# 07-FPGA.net
KiCad netlist of a schematic drawn in Altium Designer
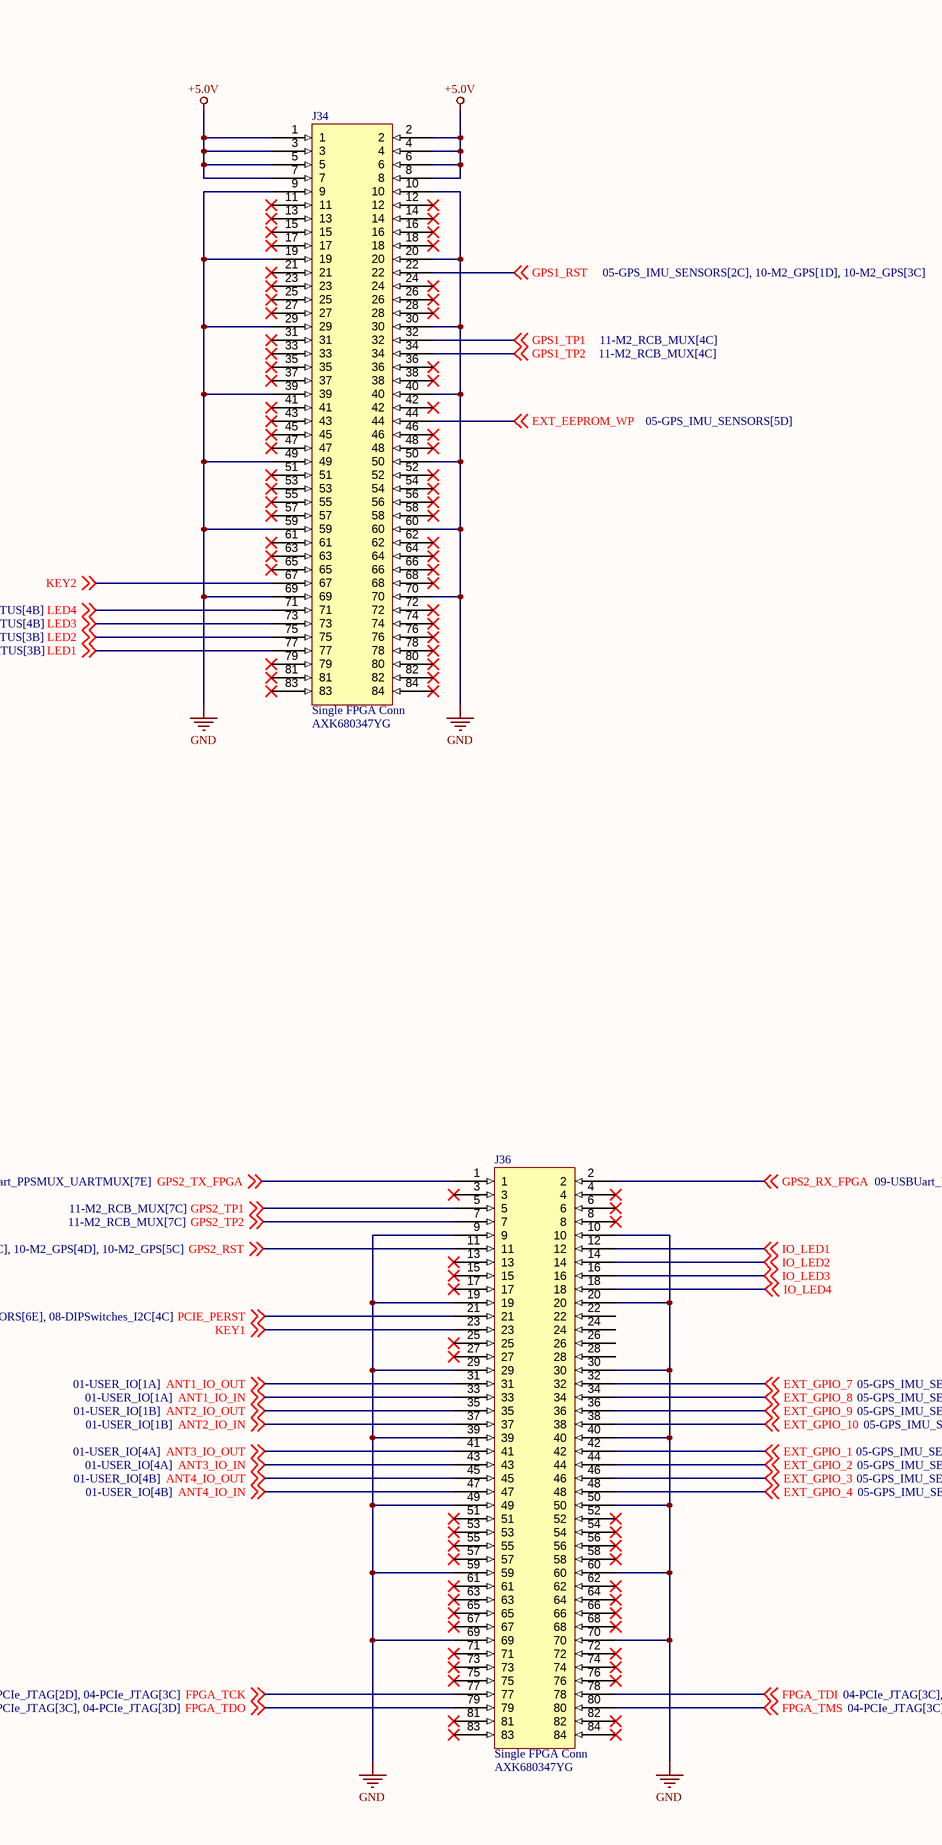
[diagram p0: 07-FPGA.SchDoc, left]
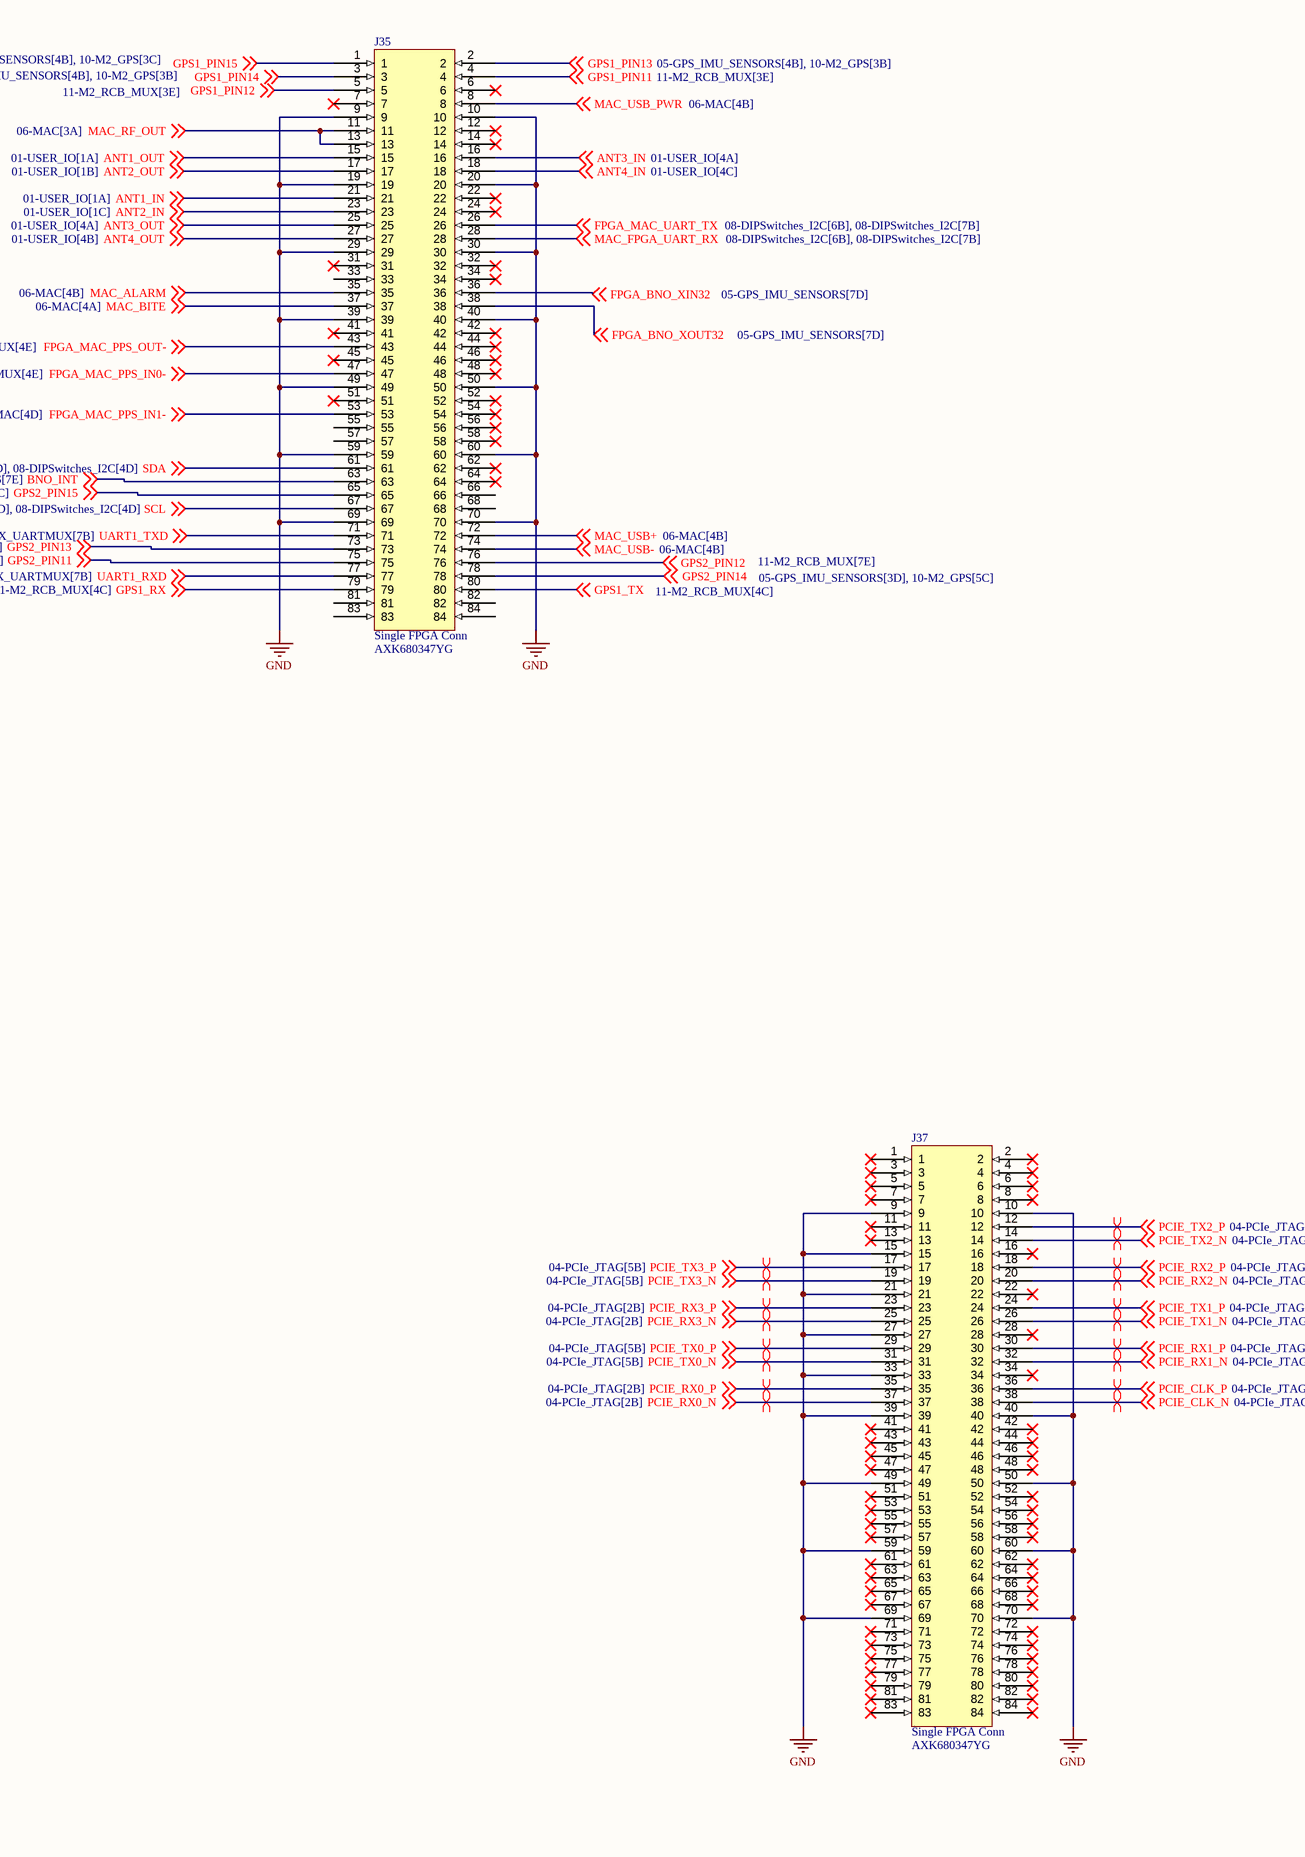
[diagram p1: 07-FPGA.SchDoc, right]

(export (version "E")
  (design (tool "Eeschema 10.0.6"))
  (components
    (comp (ref "J34")
      (value "Single FPGA Conn")
      (footprint "SingleFPGAConn")
      (fields (field (name "PART NUMBER") "AXK680347YG"))
      (libsource (lib "FPGA_CONN") (part "Single FPGA Conn"))
    )
    (comp (ref "J35")
      (value "Single FPGA Conn")
      (footprint "SingleFPGAConn")
      (fields (field (name "PART NUMBER") "AXK680347YG"))
      (libsource (lib "FPGA_CONN") (part "Single FPGA Conn"))
    )
    (comp (ref "J36")
      (value "Single FPGA Conn")
      (footprint "SingleFPGAConn")
      (fields (field (name "PART NUMBER") "AXK680347YG"))
      (libsource (lib "FPGA_CONN") (part "Single FPGA Conn"))
    )
    (comp (ref "J37")
      (value "Single FPGA Conn")
      (footprint "SingleFPGAConn")
      (fields (field (name "PART NUMBER") "AXK680347YG"))
      (libsource (lib "FPGA_CONN") (part "Single FPGA Conn"))
    )
  )
  (nets
    (net (code "1") (name "+5.0V") (class "Default")
      (node (ref "J34") (pin "1") (pinfunction "1_1") (pintype "input"))
      (node (ref "J34") (pin "2") (pinfunction "2_2") (pintype "input"))
      (node (ref "J34") (pin "3") (pinfunction "3_3") (pintype "input"))
      (node (ref "J34") (pin "4") (pinfunction "4_4") (pintype "input"))
      (node (ref "J34") (pin "5") (pinfunction "5_5") (pintype "input"))
      (node (ref "J34") (pin "6") (pinfunction "6_6") (pintype "input"))
      (node (ref "J34") (pin "7") (pinfunction "7_7") (pintype "input"))
      (node (ref "J34") (pin "8") (pinfunction "8_8") (pintype "input"))
    )
    (net (code "2") (name "ANT1_IN") (class "Default")
      (node (ref "J35") (pin "21") (pinfunction "21_21") (pintype "input"))
    )
    (net (code "3") (name "ANT1_IO_IN") (class "Default")
      (node (ref "J36") (pin "33") (pinfunction "33_33") (pintype "input"))
    )
    (net (code "4") (name "ANT1_IO_OUT") (class "Default")
      (node (ref "J36") (pin "31") (pinfunction "31_31") (pintype "input"))
    )
    (net (code "5") (name "ANT1_OUT") (class "Default")
      (node (ref "J35") (pin "15") (pinfunction "15_15") (pintype "input"))
    )
    (net (code "6") (name "ANT2_IN") (class "Default")
      (node (ref "J35") (pin "23") (pinfunction "23_23") (pintype "input"))
    )
    (net (code "7") (name "ANT2_IO_IN") (class "Default")
      (node (ref "J36") (pin "37") (pinfunction "37_37") (pintype "input"))
    )
    (net (code "8") (name "ANT2_IO_OUT") (class "Default")
      (node (ref "J36") (pin "35") (pinfunction "35_35") (pintype "input"))
    )
    (net (code "9") (name "ANT2_OUT") (class "Default")
      (node (ref "J35") (pin "17") (pinfunction "17_17") (pintype "input"))
    )
    (net (code "10") (name "ANT3_IN") (class "Default")
      (node (ref "J35") (pin "16") (pinfunction "16_16") (pintype "input"))
    )
    (net (code "11") (name "ANT3_IO_IN") (class "Default")
      (node (ref "J36") (pin "43") (pinfunction "43_43") (pintype "input"))
    )
    (net (code "12") (name "ANT3_IO_OUT") (class "Default")
      (node (ref "J36") (pin "41") (pinfunction "41_41") (pintype "input"))
    )
    (net (code "13") (name "ANT3_OUT") (class "Default")
      (node (ref "J35") (pin "25") (pinfunction "25_25") (pintype "input"))
    )
    (net (code "14") (name "ANT4_IN") (class "Default")
      (node (ref "J35") (pin "18") (pinfunction "18_18") (pintype "input"))
    )
    (net (code "15") (name "ANT4_IO_IN") (class "Default")
      (node (ref "J36") (pin "47") (pinfunction "47_47") (pintype "input"))
    )
    (net (code "16") (name "ANT4_IO_OUT") (class "Default")
      (node (ref "J36") (pin "45") (pinfunction "45_45") (pintype "input"))
    )
    (net (code "17") (name "ANT4_OUT") (class "Default")
      (node (ref "J35") (pin "27") (pinfunction "27_27") (pintype "input"))
    )
    (net (code "18") (name "BNO_INT") (class "Default")
      (node (ref "J35") (pin "63") (pinfunction "63_63") (pintype "input"))
    )
    (net (code "19") (name "EXT_EEPROM_WP") (class "Default")
      (node (ref "J34") (pin "44") (pinfunction "44_44") (pintype "input"))
    )
    (net (code "20") (name "EXT_GPIO_1") (class "Default")
      (node (ref "J36") (pin "42") (pinfunction "42_42") (pintype "input"))
    )
    (net (code "21") (name "EXT_GPIO_2") (class "Default")
      (node (ref "J36") (pin "44") (pinfunction "44_44") (pintype "input"))
    )
    (net (code "22") (name "EXT_GPIO_3") (class "Default")
      (node (ref "J36") (pin "46") (pinfunction "46_46") (pintype "input"))
    )
    (net (code "23") (name "EXT_GPIO_4") (class "Default")
      (node (ref "J36") (pin "48") (pinfunction "48_48") (pintype "input"))
    )
    (net (code "24") (name "EXT_GPIO_7") (class "Default")
      (node (ref "J36") (pin "32") (pinfunction "32_32") (pintype "input"))
    )
    (net (code "25") (name "EXT_GPIO_8") (class "Default")
      (node (ref "J36") (pin "34") (pinfunction "34_34") (pintype "input"))
    )
    (net (code "26") (name "EXT_GPIO_9") (class "Default")
      (node (ref "J36") (pin "36") (pinfunction "36_36") (pintype "input"))
    )
    (net (code "27") (name "EXT_GPIO_10") (class "Default")
      (node (ref "J36") (pin "38") (pinfunction "38_38") (pintype "input"))
    )
    (net (code "28") (name "FPGA_BNO_XIN32") (class "Default")
      (node (ref "J35") (pin "36") (pinfunction "36_36") (pintype "input"))
    )
    (net (code "29") (name "FPGA_BNO_XOUT32") (class "Default")
      (node (ref "J35") (pin "38") (pinfunction "38_38") (pintype "input"))
    )
    (net (code "30") (name "FPGA_MAC_PPS_IN0-") (class "Default")
      (node (ref "J35") (pin "47") (pinfunction "47_47") (pintype "input"))
    )
    (net (code "31") (name "FPGA_MAC_PPS_IN1-") (class "Default")
      (node (ref "J35") (pin "53") (pinfunction "53_53") (pintype "input"))
    )
    (net (code "32") (name "FPGA_MAC_PPS_OUT-") (class "Default")
      (node (ref "J35") (pin "43") (pinfunction "43_43") (pintype "input"))
    )
    (net (code "33") (name "FPGA_MAC_UART_TX") (class "Default")
      (node (ref "J35") (pin "26") (pinfunction "26_26") (pintype "input"))
    )
    (net (code "34") (name "FPGA_TCK") (class "Default")
      (node (ref "J36") (pin "77") (pinfunction "77_77") (pintype "input"))
    )
    (net (code "35") (name "FPGA_TDI") (class "Default")
      (node (ref "J36") (pin "78") (pinfunction "78_78") (pintype "input"))
    )
    (net (code "36") (name "FPGA_TDO") (class "Default")
      (node (ref "J36") (pin "79") (pinfunction "79_79") (pintype "input"))
    )
    (net (code "37") (name "FPGA_TMS") (class "Default")
      (node (ref "J36") (pin "80") (pinfunction "80_80") (pintype "input"))
    )
    (net (code "38") (name "GND") (class "Default")
      (node (ref "J34") (pin "10") (pinfunction "10_10") (pintype "input"))
      (node (ref "J34") (pin "19") (pinfunction "19_19") (pintype "input"))
      (node (ref "J34") (pin "20") (pinfunction "20_20") (pintype "input"))
      (node (ref "J34") (pin "29") (pinfunction "29_29") (pintype "input"))
      (node (ref "J34") (pin "30") (pinfunction "30_30") (pintype "input"))
      (node (ref "J34") (pin "39") (pinfunction "39_39") (pintype "input"))
      (node (ref "J34") (pin "40") (pinfunction "40_40") (pintype "input"))
      (node (ref "J34") (pin "49") (pinfunction "49_49") (pintype "input"))
      (node (ref "J34") (pin "50") (pinfunction "50_50") (pintype "input"))
      (node (ref "J34") (pin "59") (pinfunction "59_59") (pintype "input"))
      (node (ref "J34") (pin "60") (pinfunction "60_60") (pintype "input"))
      (node (ref "J34") (pin "69") (pinfunction "69_69") (pintype "input"))
      (node (ref "J34") (pin "70") (pinfunction "70_70") (pintype "input"))
      (node (ref "J34") (pin "9") (pinfunction "9_9") (pintype "input"))
      (node (ref "J35") (pin "10") (pinfunction "10_10") (pintype "input"))
      (node (ref "J35") (pin "19") (pinfunction "19_19") (pintype "input"))
      (node (ref "J35") (pin "20") (pinfunction "20_20") (pintype "input"))
      (node (ref "J35") (pin "29") (pinfunction "29_29") (pintype "input"))
      (node (ref "J35") (pin "30") (pinfunction "30_30") (pintype "input"))
      (node (ref "J35") (pin "39") (pinfunction "39_39") (pintype "input"))
      (node (ref "J35") (pin "40") (pinfunction "40_40") (pintype "input"))
      (node (ref "J35") (pin "49") (pinfunction "49_49") (pintype "input"))
      (node (ref "J35") (pin "50") (pinfunction "50_50") (pintype "input"))
      (node (ref "J35") (pin "59") (pinfunction "59_59") (pintype "input"))
      (node (ref "J35") (pin "60") (pinfunction "60_60") (pintype "input"))
      (node (ref "J35") (pin "69") (pinfunction "69_69") (pintype "input"))
      (node (ref "J35") (pin "70") (pinfunction "70_70") (pintype "input"))
      (node (ref "J35") (pin "9") (pinfunction "9_9") (pintype "input"))
      (node (ref "J36") (pin "10") (pinfunction "10_10") (pintype "input"))
      (node (ref "J36") (pin "19") (pinfunction "19_19") (pintype "input"))
      (node (ref "J36") (pin "20") (pinfunction "20_20") (pintype "input"))
      (node (ref "J36") (pin "29") (pinfunction "29_29") (pintype "input"))
      (node (ref "J36") (pin "30") (pinfunction "30_30") (pintype "input"))
      (node (ref "J36") (pin "39") (pinfunction "39_39") (pintype "input"))
      (node (ref "J36") (pin "40") (pinfunction "40_40") (pintype "input"))
      (node (ref "J36") (pin "49") (pinfunction "49_49") (pintype "input"))
      (node (ref "J36") (pin "50") (pinfunction "50_50") (pintype "input"))
      (node (ref "J36") (pin "59") (pinfunction "59_59") (pintype "input"))
      (node (ref "J36") (pin "60") (pinfunction "60_60") (pintype "input"))
      (node (ref "J36") (pin "69") (pinfunction "69_69") (pintype "input"))
      (node (ref "J36") (pin "70") (pinfunction "70_70") (pintype "input"))
      (node (ref "J36") (pin "9") (pinfunction "9_9") (pintype "input"))
      (node (ref "J37") (pin "10") (pinfunction "10_10") (pintype "input"))
      (node (ref "J37") (pin "15") (pinfunction "15_15") (pintype "input"))
      (node (ref "J37") (pin "21") (pinfunction "21_21") (pintype "input"))
      (node (ref "J37") (pin "27") (pinfunction "27_27") (pintype "input"))
      (node (ref "J37") (pin "33") (pinfunction "33_33") (pintype "input"))
      (node (ref "J37") (pin "39") (pinfunction "39_39") (pintype "input"))
      (node (ref "J37") (pin "40") (pinfunction "40_40") (pintype "input"))
      (node (ref "J37") (pin "49") (pinfunction "49_49") (pintype "input"))
      (node (ref "J37") (pin "50") (pinfunction "50_50") (pintype "input"))
      (node (ref "J37") (pin "59") (pinfunction "59_59") (pintype "input"))
      (node (ref "J37") (pin "60") (pinfunction "60_60") (pintype "input"))
      (node (ref "J37") (pin "69") (pinfunction "69_69") (pintype "input"))
      (node (ref "J37") (pin "70") (pinfunction "70_70") (pintype "input"))
      (node (ref "J37") (pin "9") (pinfunction "9_9") (pintype "input"))
    )
    (net (code "39") (name "GPS1_PIN11") (class "Default")
      (node (ref "J35") (pin "4") (pinfunction "4_4") (pintype "input"))
    )
    (net (code "40") (name "GPS1_PIN12") (class "Default")
      (node (ref "J35") (pin "5") (pinfunction "5_5") (pintype "input"))
    )
    (net (code "41") (name "GPS1_PIN13") (class "Default")
      (node (ref "J35") (pin "2") (pinfunction "2_2") (pintype "input"))
    )
    (net (code "42") (name "GPS1_PIN14") (class "Default")
      (node (ref "J35") (pin "3") (pinfunction "3_3") (pintype "input"))
    )
    (net (code "43") (name "GPS1_PIN15") (class "Default")
      (node (ref "J35") (pin "1") (pinfunction "1_1") (pintype "input"))
    )
    (net (code "44") (name "GPS1_RST") (class "Default")
      (node (ref "J34") (pin "22") (pinfunction "22_22") (pintype "input"))
    )
    (net (code "45") (name "GPS1_RX") (class "Default")
      (node (ref "J35") (pin "79") (pinfunction "79_79") (pintype "input"))
    )
    (net (code "46") (name "GPS1_TP1") (class "Default")
      (node (ref "J34") (pin "32") (pinfunction "32_32") (pintype "input"))
    )
    (net (code "47") (name "GPS1_TP2") (class "Default")
      (node (ref "J34") (pin "34") (pinfunction "34_34") (pintype "input"))
    )
    (net (code "48") (name "GPS1_TX") (class "Default")
      (node (ref "J35") (pin "80") (pinfunction "80_80") (pintype "input"))
    )
    (net (code "49") (name "GPS2_PIN11") (class "Default")
      (node (ref "J35") (pin "75") (pinfunction "75_75") (pintype "input"))
    )
    (net (code "50") (name "GPS2_PIN12") (class "Default")
      (node (ref "J35") (pin "76") (pinfunction "76_76") (pintype "input"))
    )
    (net (code "51") (name "GPS2_PIN13") (class "Default")
      (node (ref "J35") (pin "73") (pinfunction "73_73") (pintype "input"))
    )
    (net (code "52") (name "GPS2_PIN14") (class "Default")
      (node (ref "J35") (pin "78") (pinfunction "78_78") (pintype "input"))
    )
    (net (code "53") (name "GPS2_PIN15") (class "Default")
      (node (ref "J35") (pin "65") (pinfunction "65_65") (pintype "input"))
    )
    (net (code "54") (name "GPS2_RST") (class "Default")
      (node (ref "J36") (pin "11") (pinfunction "11_11") (pintype "input"))
    )
    (net (code "55") (name "GPS2_RX_FPGA") (class "Default")
      (node (ref "J36") (pin "2") (pinfunction "2_2") (pintype "input"))
    )
    (net (code "56") (name "GPS2_TP1") (class "Default")
      (node (ref "J36") (pin "5") (pinfunction "5_5") (pintype "input"))
    )
    (net (code "57") (name "GPS2_TP2") (class "Default")
      (node (ref "J36") (pin "7") (pinfunction "7_7") (pintype "input"))
    )
    (net (code "58") (name "GPS2_TX_FPGA") (class "Default")
      (node (ref "J36") (pin "1") (pinfunction "1_1") (pintype "input"))
    )
    (net (code "59") (name "IO_LED1") (class "Default")
      (node (ref "J36") (pin "12") (pinfunction "12_12") (pintype "input"))
    )
    (net (code "60") (name "IO_LED2") (class "Default")
      (node (ref "J36") (pin "14") (pinfunction "14_14") (pintype "input"))
    )
    (net (code "61") (name "IO_LED3") (class "Default")
      (node (ref "J36") (pin "16") (pinfunction "16_16") (pintype "input"))
    )
    (net (code "62") (name "IO_LED4") (class "Default")
      (node (ref "J36") (pin "18") (pinfunction "18_18") (pintype "input"))
    )
    (net (code "63") (name "KEY1") (class "Default")
      (node (ref "J36") (pin "23") (pinfunction "23_23") (pintype "input"))
    )
    (net (code "64") (name "KEY2") (class "Default")
      (node (ref "J34") (pin "67") (pinfunction "67_67") (pintype "input"))
    )
    (net (code "65") (name "LED1") (class "Default")
      (node (ref "J34") (pin "77") (pinfunction "77_77") (pintype "input"))
    )
    (net (code "66") (name "LED2") (class "Default")
      (node (ref "J34") (pin "75") (pinfunction "75_75") (pintype "input"))
    )
    (net (code "67") (name "LED3") (class "Default")
      (node (ref "J34") (pin "73") (pinfunction "73_73") (pintype "input"))
    )
    (net (code "68") (name "LED4") (class "Default")
      (node (ref "J34") (pin "71") (pinfunction "71_71") (pintype "input"))
    )
    (net (code "69") (name "MAC_ALARM") (class "Default")
      (node (ref "J35") (pin "35") (pinfunction "35_35") (pintype "input"))
    )
    (net (code "70") (name "MAC_BITE") (class "Default")
      (node (ref "J35") (pin "37") (pinfunction "37_37") (pintype "input"))
    )
    (net (code "71") (name "MAC_FPGA_UART_RX") (class "Default")
      (node (ref "J35") (pin "28") (pinfunction "28_28") (pintype "input"))
    )
    (net (code "72") (name "MAC_RF_OUT") (class "Default")
      (node (ref "J35") (pin "11") (pinfunction "11_11") (pintype "input"))
      (node (ref "J35") (pin "13") (pinfunction "13_13") (pintype "input"))
    )
    (net (code "73") (name "MAC_USB+") (class "Default")
      (node (ref "J35") (pin "72") (pinfunction "72_72") (pintype "input"))
    )
    (net (code "74") (name "MAC_USB-") (class "Default")
      (node (ref "J35") (pin "74") (pinfunction "74_74") (pintype "input"))
    )
    (net (code "75") (name "MAC_USB_PWR") (class "Default")
      (node (ref "J35") (pin "8") (pinfunction "8_8") (pintype "input"))
    )
    (net (code "76") (name "PCIE_CLK_N") (class "Default")
      (node (ref "J37") (pin "38") (pinfunction "38_38") (pintype "input"))
    )
    (net (code "77") (name "PCIE_CLK_P") (class "Default")
      (node (ref "J37") (pin "36") (pinfunction "36_36") (pintype "input"))
    )
    (net (code "78") (name "PCIE_PERST") (class "Default")
      (node (ref "J36") (pin "21") (pinfunction "21_21") (pintype "input"))
    )
    (net (code "79") (name "PCIE_RX0_N") (class "Default")
      (node (ref "J37") (pin "37") (pinfunction "37_37") (pintype "input"))
    )
    (net (code "80") (name "PCIE_RX0_P") (class "Default")
      (node (ref "J37") (pin "35") (pinfunction "35_35") (pintype "input"))
    )
    (net (code "81") (name "PCIE_RX1_N") (class "Default")
      (node (ref "J37") (pin "32") (pinfunction "32_32") (pintype "input"))
    )
    (net (code "82") (name "PCIE_RX1_P") (class "Default")
      (node (ref "J37") (pin "30") (pinfunction "30_30") (pintype "input"))
    )
    (net (code "83") (name "PCIE_RX2_N") (class "Default")
      (node (ref "J37") (pin "20") (pinfunction "20_20") (pintype "input"))
    )
    (net (code "84") (name "PCIE_RX2_P") (class "Default")
      (node (ref "J37") (pin "18") (pinfunction "18_18") (pintype "input"))
    )
    (net (code "85") (name "PCIE_RX3_N") (class "Default")
      (node (ref "J37") (pin "25") (pinfunction "25_25") (pintype "input"))
    )
    (net (code "86") (name "PCIE_RX3_P") (class "Default")
      (node (ref "J37") (pin "23") (pinfunction "23_23") (pintype "input"))
    )
    (net (code "87") (name "PCIE_TX0_N") (class "Default")
      (node (ref "J37") (pin "31") (pinfunction "31_31") (pintype "input"))
    )
    (net (code "88") (name "PCIE_TX0_P") (class "Default")
      (node (ref "J37") (pin "29") (pinfunction "29_29") (pintype "input"))
    )
    (net (code "89") (name "PCIE_TX1_N") (class "Default")
      (node (ref "J37") (pin "26") (pinfunction "26_26") (pintype "input"))
    )
    (net (code "90") (name "PCIE_TX1_P") (class "Default")
      (node (ref "J37") (pin "24") (pinfunction "24_24") (pintype "input"))
    )
    (net (code "91") (name "PCIE_TX2_N") (class "Default")
      (node (ref "J37") (pin "14") (pinfunction "14_14") (pintype "input"))
    )
    (net (code "92") (name "PCIE_TX2_P") (class "Default")
      (node (ref "J37") (pin "12") (pinfunction "12_12") (pintype "input"))
    )
    (net (code "93") (name "PCIE_TX3_N") (class "Default")
      (node (ref "J37") (pin "19") (pinfunction "19_19") (pintype "input"))
    )
    (net (code "94") (name "PCIE_TX3_P") (class "Default")
      (node (ref "J37") (pin "17") (pinfunction "17_17") (pintype "input"))
    )
    (net (code "95") (name "SCL") (class "Default")
      (node (ref "J35") (pin "67") (pinfunction "67_67") (pintype "input"))
    )
    (net (code "96") (name "SDA") (class "Default")
      (node (ref "J35") (pin "61") (pinfunction "61_61") (pintype "input"))
    )
    (net (code "97") (name "UART1_RXD") (class "Default")
      (node (ref "J35") (pin "77") (pinfunction "77_77") (pintype "input"))
    )
    (net (code "98") (name "UART1_TXD") (class "Default")
      (node (ref "J35") (pin "71") (pinfunction "71_71") (pintype "input"))
    )
    (net (code "99") (name "unconnected-(J34-Pad11)") (class "Default")
      (node (ref "J34") (pin "11") (pinfunction "11_11") (pintype "input+no_connect"))
    )
    (net (code "100") (name "unconnected-(J34-Pad12)") (class "Default")
      (node (ref "J34") (pin "12") (pinfunction "12_12") (pintype "input+no_connect"))
    )
    (net (code "101") (name "unconnected-(J34-Pad13)") (class "Default")
      (node (ref "J34") (pin "13") (pinfunction "13_13") (pintype "input+no_connect"))
    )
    (net (code "102") (name "unconnected-(J34-Pad14)") (class "Default")
      (node (ref "J34") (pin "14") (pinfunction "14_14") (pintype "input+no_connect"))
    )
    (net (code "103") (name "unconnected-(J34-Pad15)") (class "Default")
      (node (ref "J34") (pin "15") (pinfunction "15_15") (pintype "input+no_connect"))
    )
    (net (code "104") (name "unconnected-(J34-Pad16)") (class "Default")
      (node (ref "J34") (pin "16") (pinfunction "16_16") (pintype "input+no_connect"))
    )
    (net (code "105") (name "unconnected-(J34-Pad17)") (class "Default")
      (node (ref "J34") (pin "17") (pinfunction "17_17") (pintype "input+no_connect"))
    )
    (net (code "106") (name "unconnected-(J34-Pad18)") (class "Default")
      (node (ref "J34") (pin "18") (pinfunction "18_18") (pintype "input+no_connect"))
    )
    (net (code "107") (name "unconnected-(J34-Pad21)") (class "Default")
      (node (ref "J34") (pin "21") (pinfunction "21_21") (pintype "input+no_connect"))
    )
    (net (code "108") (name "unconnected-(J34-Pad23)") (class "Default")
      (node (ref "J34") (pin "23") (pinfunction "23_23") (pintype "input+no_connect"))
    )
    (net (code "109") (name "unconnected-(J34-Pad24)") (class "Default")
      (node (ref "J34") (pin "24") (pinfunction "24_24") (pintype "input+no_connect"))
    )
    (net (code "110") (name "unconnected-(J34-Pad25)") (class "Default")
      (node (ref "J34") (pin "25") (pinfunction "25_25") (pintype "input+no_connect"))
    )
    (net (code "111") (name "unconnected-(J34-Pad26)") (class "Default")
      (node (ref "J34") (pin "26") (pinfunction "26_26") (pintype "input+no_connect"))
    )
    (net (code "112") (name "unconnected-(J34-Pad27)") (class "Default")
      (node (ref "J34") (pin "27") (pinfunction "27_27") (pintype "input+no_connect"))
    )
    (net (code "113") (name "unconnected-(J34-Pad28)") (class "Default")
      (node (ref "J34") (pin "28") (pinfunction "28_28") (pintype "input+no_connect"))
    )
    (net (code "114") (name "unconnected-(J34-Pad31)") (class "Default")
      (node (ref "J34") (pin "31") (pinfunction "31_31") (pintype "input+no_connect"))
    )
    (net (code "115") (name "unconnected-(J34-Pad33)") (class "Default")
      (node (ref "J34") (pin "33") (pinfunction "33_33") (pintype "input+no_connect"))
    )
    (net (code "116") (name "unconnected-(J34-Pad35)") (class "Default")
      (node (ref "J34") (pin "35") (pinfunction "35_35") (pintype "input+no_connect"))
    )
    (net (code "117") (name "unconnected-(J34-Pad36)") (class "Default")
      (node (ref "J34") (pin "36") (pinfunction "36_36") (pintype "input+no_connect"))
    )
    (net (code "118") (name "unconnected-(J34-Pad37)") (class "Default")
      (node (ref "J34") (pin "37") (pinfunction "37_37") (pintype "input+no_connect"))
    )
    (net (code "119") (name "unconnected-(J34-Pad38)") (class "Default")
      (node (ref "J34") (pin "38") (pinfunction "38_38") (pintype "input+no_connect"))
    )
    (net (code "120") (name "unconnected-(J34-Pad41)") (class "Default")
      (node (ref "J34") (pin "41") (pinfunction "41_41") (pintype "input+no_connect"))
    )
    (net (code "121") (name "unconnected-(J34-Pad42)") (class "Default")
      (node (ref "J34") (pin "42") (pinfunction "42_42") (pintype "input+no_connect"))
    )
    (net (code "122") (name "unconnected-(J34-Pad43)") (class "Default")
      (node (ref "J34") (pin "43") (pinfunction "43_43") (pintype "input+no_connect"))
    )
    (net (code "123") (name "unconnected-(J34-Pad45)") (class "Default")
      (node (ref "J34") (pin "45") (pinfunction "45_45") (pintype "input+no_connect"))
    )
    (net (code "124") (name "unconnected-(J34-Pad46)") (class "Default")
      (node (ref "J34") (pin "46") (pinfunction "46_46") (pintype "input+no_connect"))
    )
    (net (code "125") (name "unconnected-(J34-Pad47)") (class "Default")
      (node (ref "J34") (pin "47") (pinfunction "47_47") (pintype "input+no_connect"))
    )
    (net (code "126") (name "unconnected-(J34-Pad48)") (class "Default")
      (node (ref "J34") (pin "48") (pinfunction "48_48") (pintype "input+no_connect"))
    )
    (net (code "127") (name "unconnected-(J34-Pad51)") (class "Default")
      (node (ref "J34") (pin "51") (pinfunction "51_51") (pintype "input+no_connect"))
    )
    (net (code "128") (name "unconnected-(J34-Pad52)") (class "Default")
      (node (ref "J34") (pin "52") (pinfunction "52_52") (pintype "input+no_connect"))
    )
    (net (code "129") (name "unconnected-(J34-Pad53)") (class "Default")
      (node (ref "J34") (pin "53") (pinfunction "53_53") (pintype "input+no_connect"))
    )
    (net (code "130") (name "unconnected-(J34-Pad54)") (class "Default")
      (node (ref "J34") (pin "54") (pinfunction "54_54") (pintype "input+no_connect"))
    )
    (net (code "131") (name "unconnected-(J34-Pad55)") (class "Default")
      (node (ref "J34") (pin "55") (pinfunction "55_55") (pintype "input+no_connect"))
    )
    (net (code "132") (name "unconnected-(J34-Pad56)") (class "Default")
      (node (ref "J34") (pin "56") (pinfunction "56_56") (pintype "input+no_connect"))
    )
    (net (code "133") (name "unconnected-(J34-Pad57)") (class "Default")
      (node (ref "J34") (pin "57") (pinfunction "57_57") (pintype "input+no_connect"))
    )
    (net (code "134") (name "unconnected-(J34-Pad58)") (class "Default")
      (node (ref "J34") (pin "58") (pinfunction "58_58") (pintype "input+no_connect"))
    )
    (net (code "135") (name "unconnected-(J34-Pad61)") (class "Default")
      (node (ref "J34") (pin "61") (pinfunction "61_61") (pintype "input+no_connect"))
    )
    (net (code "136") (name "unconnected-(J34-Pad62)") (class "Default")
      (node (ref "J34") (pin "62") (pinfunction "62_62") (pintype "input+no_connect"))
    )
    (net (code "137") (name "unconnected-(J34-Pad63)") (class "Default")
      (node (ref "J34") (pin "63") (pinfunction "63_63") (pintype "input+no_connect"))
    )
    (net (code "138") (name "unconnected-(J34-Pad64)") (class "Default")
      (node (ref "J34") (pin "64") (pinfunction "64_64") (pintype "input+no_connect"))
    )
    (net (code "139") (name "unconnected-(J34-Pad65)") (class "Default")
      (node (ref "J34") (pin "65") (pinfunction "65_65") (pintype "input+no_connect"))
    )
    (net (code "140") (name "unconnected-(J34-Pad66)") (class "Default")
      (node (ref "J34") (pin "66") (pinfunction "66_66") (pintype "input+no_connect"))
    )
    (net (code "141") (name "unconnected-(J34-Pad68)") (class "Default")
      (node (ref "J34") (pin "68") (pinfunction "68_68") (pintype "input+no_connect"))
    )
    (net (code "142") (name "unconnected-(J34-Pad72)") (class "Default")
      (node (ref "J34") (pin "72") (pinfunction "72_72") (pintype "input+no_connect"))
    )
    (net (code "143") (name "unconnected-(J34-Pad74)") (class "Default")
      (node (ref "J34") (pin "74") (pinfunction "74_74") (pintype "input+no_connect"))
    )
    (net (code "144") (name "unconnected-(J34-Pad76)") (class "Default")
      (node (ref "J34") (pin "76") (pinfunction "76_76") (pintype "input+no_connect"))
    )
    (net (code "145") (name "unconnected-(J34-Pad78)") (class "Default")
      (node (ref "J34") (pin "78") (pinfunction "78_78") (pintype "input+no_connect"))
    )
    (net (code "146") (name "unconnected-(J34-Pad79)") (class "Default")
      (node (ref "J34") (pin "79") (pinfunction "79_79") (pintype "input+no_connect"))
    )
    (net (code "147") (name "unconnected-(J34-Pad80)") (class "Default")
      (node (ref "J34") (pin "80") (pinfunction "80_80") (pintype "input+no_connect"))
    )
    (net (code "148") (name "unconnected-(J34-Pad81)") (class "Default")
      (node (ref "J34") (pin "81") (pinfunction "81_81") (pintype "input+no_connect"))
    )
    (net (code "149") (name "unconnected-(J34-Pad82)") (class "Default")
      (node (ref "J34") (pin "82") (pinfunction "82_82") (pintype "input+no_connect"))
    )
    (net (code "150") (name "unconnected-(J34-Pad83)") (class "Default")
      (node (ref "J34") (pin "83") (pinfunction "83_83") (pintype "input+no_connect"))
    )
    (net (code "151") (name "unconnected-(J34-Pad84)") (class "Default")
      (node (ref "J34") (pin "84") (pinfunction "84_84") (pintype "input+no_connect"))
    )
    (net (code "152") (name "unconnected-(J35-Pad6)") (class "Default")
      (node (ref "J35") (pin "6") (pinfunction "6_6") (pintype "input+no_connect"))
    )
    (net (code "153") (name "unconnected-(J35-Pad7)") (class "Default")
      (node (ref "J35") (pin "7") (pinfunction "7_7") (pintype "input+no_connect"))
    )
    (net (code "154") (name "unconnected-(J35-Pad12)") (class "Default")
      (node (ref "J35") (pin "12") (pinfunction "12_12") (pintype "input+no_connect"))
    )
    (net (code "155") (name "unconnected-(J35-Pad14)") (class "Default")
      (node (ref "J35") (pin "14") (pinfunction "14_14") (pintype "input+no_connect"))
    )
    (net (code "156") (name "unconnected-(J35-Pad22)") (class "Default")
      (node (ref "J35") (pin "22") (pinfunction "22_22") (pintype "input+no_connect"))
    )
    (net (code "157") (name "unconnected-(J35-Pad24)") (class "Default")
      (node (ref "J35") (pin "24") (pinfunction "24_24") (pintype "input+no_connect"))
    )
    (net (code "158") (name "unconnected-(J35-Pad31)") (class "Default")
      (node (ref "J35") (pin "31") (pinfunction "31_31") (pintype "input+no_connect"))
    )
    (net (code "159") (name "unconnected-(J35-Pad32)") (class "Default")
      (node (ref "J35") (pin "32") (pinfunction "32_32") (pintype "input+no_connect"))
    )
    (net (code "160") (name "unconnected-(J35-Pad33)") (class "Default")
      (node (ref "J35") (pin "33") (pinfunction "33_33") (pintype "input"))
    )
    (net (code "161") (name "unconnected-(J35-Pad34)") (class "Default")
      (node (ref "J35") (pin "34") (pinfunction "34_34") (pintype "input+no_connect"))
    )
    (net (code "162") (name "unconnected-(J35-Pad41)") (class "Default")
      (node (ref "J35") (pin "41") (pinfunction "41_41") (pintype "input+no_connect"))
    )
    (net (code "163") (name "unconnected-(J35-Pad42)") (class "Default")
      (node (ref "J35") (pin "42") (pinfunction "42_42") (pintype "input+no_connect"))
    )
    (net (code "164") (name "unconnected-(J35-Pad44)") (class "Default")
      (node (ref "J35") (pin "44") (pinfunction "44_44") (pintype "input+no_connect"))
    )
    (net (code "165") (name "unconnected-(J35-Pad45)") (class "Default")
      (node (ref "J35") (pin "45") (pinfunction "45_45") (pintype "input+no_connect"))
    )
    (net (code "166") (name "unconnected-(J35-Pad46)") (class "Default")
      (node (ref "J35") (pin "46") (pinfunction "46_46") (pintype "input+no_connect"))
    )
    (net (code "167") (name "unconnected-(J35-Pad48)") (class "Default")
      (node (ref "J35") (pin "48") (pinfunction "48_48") (pintype "input+no_connect"))
    )
    (net (code "168") (name "unconnected-(J35-Pad51)") (class "Default")
      (node (ref "J35") (pin "51") (pinfunction "51_51") (pintype "input+no_connect"))
    )
    (net (code "169") (name "unconnected-(J35-Pad52)") (class "Default")
      (node (ref "J35") (pin "52") (pinfunction "52_52") (pintype "input+no_connect"))
    )
    (net (code "170") (name "unconnected-(J35-Pad54)") (class "Default")
      (node (ref "J35") (pin "54") (pinfunction "54_54") (pintype "input+no_connect"))
    )
    (net (code "171") (name "unconnected-(J35-Pad55)") (class "Default")
      (node (ref "J35") (pin "55") (pinfunction "55_55") (pintype "input"))
    )
    (net (code "172") (name "unconnected-(J35-Pad56)") (class "Default")
      (node (ref "J35") (pin "56") (pinfunction "56_56") (pintype "input+no_connect"))
    )
    (net (code "173") (name "unconnected-(J35-Pad57)") (class "Default")
      (node (ref "J35") (pin "57") (pinfunction "57_57") (pintype "input"))
    )
    (net (code "174") (name "unconnected-(J35-Pad58)") (class "Default")
      (node (ref "J35") (pin "58") (pinfunction "58_58") (pintype "input+no_connect"))
    )
    (net (code "175") (name "unconnected-(J35-Pad62)") (class "Default")
      (node (ref "J35") (pin "62") (pinfunction "62_62") (pintype "input+no_connect"))
    )
    (net (code "176") (name "unconnected-(J35-Pad64)") (class "Default")
      (node (ref "J35") (pin "64") (pinfunction "64_64") (pintype "input+no_connect"))
    )
    (net (code "177") (name "unconnected-(J35-Pad66)") (class "Default")
      (node (ref "J35") (pin "66") (pinfunction "66_66") (pintype "input"))
    )
    (net (code "178") (name "unconnected-(J35-Pad68)") (class "Default")
      (node (ref "J35") (pin "68") (pinfunction "68_68") (pintype "input"))
    )
    (net (code "179") (name "unconnected-(J35-Pad81)") (class "Default")
      (node (ref "J35") (pin "81") (pinfunction "81_81") (pintype "input"))
    )
    (net (code "180") (name "unconnected-(J35-Pad82)") (class "Default")
      (node (ref "J35") (pin "82") (pinfunction "82_82") (pintype "input"))
    )
    (net (code "181") (name "unconnected-(J35-Pad83)") (class "Default")
      (node (ref "J35") (pin "83") (pinfunction "83_83") (pintype "input"))
    )
    (net (code "182") (name "unconnected-(J35-Pad84)") (class "Default")
      (node (ref "J35") (pin "84") (pinfunction "84_84") (pintype "input"))
    )
    (net (code "183") (name "unconnected-(J36-Pad3)") (class "Default")
      (node (ref "J36") (pin "3") (pinfunction "3_3") (pintype "input+no_connect"))
    )
    (net (code "184") (name "unconnected-(J36-Pad4)") (class "Default")
      (node (ref "J36") (pin "4") (pinfunction "4_4") (pintype "input+no_connect"))
    )
    (net (code "185") (name "unconnected-(J36-Pad6)") (class "Default")
      (node (ref "J36") (pin "6") (pinfunction "6_6") (pintype "input+no_connect"))
    )
    (net (code "186") (name "unconnected-(J36-Pad8)") (class "Default")
      (node (ref "J36") (pin "8") (pinfunction "8_8") (pintype "input+no_connect"))
    )
    (net (code "187") (name "unconnected-(J36-Pad13)") (class "Default")
      (node (ref "J36") (pin "13") (pinfunction "13_13") (pintype "input+no_connect"))
    )
    (net (code "188") (name "unconnected-(J36-Pad15)") (class "Default")
      (node (ref "J36") (pin "15") (pinfunction "15_15") (pintype "input+no_connect"))
    )
    (net (code "189") (name "unconnected-(J36-Pad17)") (class "Default")
      (node (ref "J36") (pin "17") (pinfunction "17_17") (pintype "input+no_connect"))
    )
    (net (code "190") (name "unconnected-(J36-Pad22)") (class "Default")
      (node (ref "J36") (pin "22") (pinfunction "22_22") (pintype "input"))
    )
    (net (code "191") (name "unconnected-(J36-Pad24)") (class "Default")
      (node (ref "J36") (pin "24") (pinfunction "24_24") (pintype "input"))
    )
    (net (code "192") (name "unconnected-(J36-Pad25)") (class "Default")
      (node (ref "J36") (pin "25") (pinfunction "25_25") (pintype "input+no_connect"))
    )
    (net (code "193") (name "unconnected-(J36-Pad26)") (class "Default")
      (node (ref "J36") (pin "26") (pinfunction "26_26") (pintype "input"))
    )
    (net (code "194") (name "unconnected-(J36-Pad27)") (class "Default")
      (node (ref "J36") (pin "27") (pinfunction "27_27") (pintype "input+no_connect"))
    )
    (net (code "195") (name "unconnected-(J36-Pad28)") (class "Default")
      (node (ref "J36") (pin "28") (pinfunction "28_28") (pintype "input"))
    )
    (net (code "196") (name "unconnected-(J36-Pad51)") (class "Default")
      (node (ref "J36") (pin "51") (pinfunction "51_51") (pintype "input+no_connect"))
    )
    (net (code "197") (name "unconnected-(J36-Pad52)") (class "Default")
      (node (ref "J36") (pin "52") (pinfunction "52_52") (pintype "input+no_connect"))
    )
    (net (code "198") (name "unconnected-(J36-Pad53)") (class "Default")
      (node (ref "J36") (pin "53") (pinfunction "53_53") (pintype "input+no_connect"))
    )
    (net (code "199") (name "unconnected-(J36-Pad54)") (class "Default")
      (node (ref "J36") (pin "54") (pinfunction "54_54") (pintype "input+no_connect"))
    )
    (net (code "200") (name "unconnected-(J36-Pad55)") (class "Default")
      (node (ref "J36") (pin "55") (pinfunction "55_55") (pintype "input+no_connect"))
    )
    (net (code "201") (name "unconnected-(J36-Pad56)") (class "Default")
      (node (ref "J36") (pin "56") (pinfunction "56_56") (pintype "input+no_connect"))
    )
    (net (code "202") (name "unconnected-(J36-Pad57)") (class "Default")
      (node (ref "J36") (pin "57") (pinfunction "57_57") (pintype "input+no_connect"))
    )
    (net (code "203") (name "unconnected-(J36-Pad58)") (class "Default")
      (node (ref "J36") (pin "58") (pinfunction "58_58") (pintype "input+no_connect"))
    )
    (net (code "204") (name "unconnected-(J36-Pad61)") (class "Default")
      (node (ref "J36") (pin "61") (pinfunction "61_61") (pintype "input+no_connect"))
    )
    (net (code "205") (name "unconnected-(J36-Pad62)") (class "Default")
      (node (ref "J36") (pin "62") (pinfunction "62_62") (pintype "input+no_connect"))
    )
    (net (code "206") (name "unconnected-(J36-Pad63)") (class "Default")
      (node (ref "J36") (pin "63") (pinfunction "63_63") (pintype "input+no_connect"))
    )
    (net (code "207") (name "unconnected-(J36-Pad64)") (class "Default")
      (node (ref "J36") (pin "64") (pinfunction "64_64") (pintype "input+no_connect"))
    )
    (net (code "208") (name "unconnected-(J36-Pad65)") (class "Default")
      (node (ref "J36") (pin "65") (pinfunction "65_65") (pintype "input+no_connect"))
    )
    (net (code "209") (name "unconnected-(J36-Pad66)") (class "Default")
      (node (ref "J36") (pin "66") (pinfunction "66_66") (pintype "input+no_connect"))
    )
    (net (code "210") (name "unconnected-(J36-Pad67)") (class "Default")
      (node (ref "J36") (pin "67") (pinfunction "67_67") (pintype "input+no_connect"))
    )
    (net (code "211") (name "unconnected-(J36-Pad68)") (class "Default")
      (node (ref "J36") (pin "68") (pinfunction "68_68") (pintype "input+no_connect"))
    )
    (net (code "212") (name "unconnected-(J36-Pad71)") (class "Default")
      (node (ref "J36") (pin "71") (pinfunction "71_71") (pintype "input+no_connect"))
    )
    (net (code "213") (name "unconnected-(J36-Pad72)") (class "Default")
      (node (ref "J36") (pin "72") (pinfunction "72_72") (pintype "input+no_connect"))
    )
    (net (code "214") (name "unconnected-(J36-Pad73)") (class "Default")
      (node (ref "J36") (pin "73") (pinfunction "73_73") (pintype "input+no_connect"))
    )
    (net (code "215") (name "unconnected-(J36-Pad74)") (class "Default")
      (node (ref "J36") (pin "74") (pinfunction "74_74") (pintype "input+no_connect"))
    )
    (net (code "216") (name "unconnected-(J36-Pad75)") (class "Default")
      (node (ref "J36") (pin "75") (pinfunction "75_75") (pintype "input+no_connect"))
    )
    (net (code "217") (name "unconnected-(J36-Pad76)") (class "Default")
      (node (ref "J36") (pin "76") (pinfunction "76_76") (pintype "input+no_connect"))
    )
    (net (code "218") (name "unconnected-(J36-Pad81)") (class "Default")
      (node (ref "J36") (pin "81") (pinfunction "81_81") (pintype "input+no_connect"))
    )
    (net (code "219") (name "unconnected-(J36-Pad82)") (class "Default")
      (node (ref "J36") (pin "82") (pinfunction "82_82") (pintype "input+no_connect"))
    )
    (net (code "220") (name "unconnected-(J36-Pad83)") (class "Default")
      (node (ref "J36") (pin "83") (pinfunction "83_83") (pintype "input+no_connect"))
    )
    (net (code "221") (name "unconnected-(J36-Pad84)") (class "Default")
      (node (ref "J36") (pin "84") (pinfunction "84_84") (pintype "input+no_connect"))
    )
    (net (code "222") (name "unconnected-(J37-Pad1)") (class "Default")
      (node (ref "J37") (pin "1") (pinfunction "1_1") (pintype "input+no_connect"))
    )
    (net (code "223") (name "unconnected-(J37-Pad2)") (class "Default")
      (node (ref "J37") (pin "2") (pinfunction "2_2") (pintype "input+no_connect"))
    )
    (net (code "224") (name "unconnected-(J37-Pad3)") (class "Default")
      (node (ref "J37") (pin "3") (pinfunction "3_3") (pintype "input+no_connect"))
    )
    (net (code "225") (name "unconnected-(J37-Pad4)") (class "Default")
      (node (ref "J37") (pin "4") (pinfunction "4_4") (pintype "input+no_connect"))
    )
    (net (code "226") (name "unconnected-(J37-Pad5)") (class "Default")
      (node (ref "J37") (pin "5") (pinfunction "5_5") (pintype "input+no_connect"))
    )
    (net (code "227") (name "unconnected-(J37-Pad6)") (class "Default")
      (node (ref "J37") (pin "6") (pinfunction "6_6") (pintype "input+no_connect"))
    )
    (net (code "228") (name "unconnected-(J37-Pad7)") (class "Default")
      (node (ref "J37") (pin "7") (pinfunction "7_7") (pintype "input+no_connect"))
    )
    (net (code "229") (name "unconnected-(J37-Pad8)") (class "Default")
      (node (ref "J37") (pin "8") (pinfunction "8_8") (pintype "input+no_connect"))
    )
    (net (code "230") (name "unconnected-(J37-Pad11)") (class "Default")
      (node (ref "J37") (pin "11") (pinfunction "11_11") (pintype "input+no_connect"))
    )
    (net (code "231") (name "unconnected-(J37-Pad13)") (class "Default")
      (node (ref "J37") (pin "13") (pinfunction "13_13") (pintype "input+no_connect"))
    )
    (net (code "232") (name "unconnected-(J37-Pad16)") (class "Default")
      (node (ref "J37") (pin "16") (pinfunction "16_16") (pintype "input+no_connect"))
    )
    (net (code "233") (name "unconnected-(J37-Pad22)") (class "Default")
      (node (ref "J37") (pin "22") (pinfunction "22_22") (pintype "input+no_connect"))
    )
    (net (code "234") (name "unconnected-(J37-Pad28)") (class "Default")
      (node (ref "J37") (pin "28") (pinfunction "28_28") (pintype "input+no_connect"))
    )
    (net (code "235") (name "unconnected-(J37-Pad34)") (class "Default")
      (node (ref "J37") (pin "34") (pinfunction "34_34") (pintype "input+no_connect"))
    )
    (net (code "236") (name "unconnected-(J37-Pad41)") (class "Default")
      (node (ref "J37") (pin "41") (pinfunction "41_41") (pintype "input+no_connect"))
    )
    (net (code "237") (name "unconnected-(J37-Pad42)") (class "Default")
      (node (ref "J37") (pin "42") (pinfunction "42_42") (pintype "input+no_connect"))
    )
    (net (code "238") (name "unconnected-(J37-Pad43)") (class "Default")
      (node (ref "J37") (pin "43") (pinfunction "43_43") (pintype "input+no_connect"))
    )
    (net (code "239") (name "unconnected-(J37-Pad44)") (class "Default")
      (node (ref "J37") (pin "44") (pinfunction "44_44") (pintype "input+no_connect"))
    )
    (net (code "240") (name "unconnected-(J37-Pad45)") (class "Default")
      (node (ref "J37") (pin "45") (pinfunction "45_45") (pintype "input+no_connect"))
    )
    (net (code "241") (name "unconnected-(J37-Pad46)") (class "Default")
      (node (ref "J37") (pin "46") (pinfunction "46_46") (pintype "input+no_connect"))
    )
    (net (code "242") (name "unconnected-(J37-Pad47)") (class "Default")
      (node (ref "J37") (pin "47") (pinfunction "47_47") (pintype "input+no_connect"))
    )
    (net (code "243") (name "unconnected-(J37-Pad48)") (class "Default")
      (node (ref "J37") (pin "48") (pinfunction "48_48") (pintype "input+no_connect"))
    )
    (net (code "244") (name "unconnected-(J37-Pad51)") (class "Default")
      (node (ref "J37") (pin "51") (pinfunction "51_51") (pintype "input+no_connect"))
    )
    (net (code "245") (name "unconnected-(J37-Pad52)") (class "Default")
      (node (ref "J37") (pin "52") (pinfunction "52_52") (pintype "input+no_connect"))
    )
    (net (code "246") (name "unconnected-(J37-Pad53)") (class "Default")
      (node (ref "J37") (pin "53") (pinfunction "53_53") (pintype "input+no_connect"))
    )
    (net (code "247") (name "unconnected-(J37-Pad54)") (class "Default")
      (node (ref "J37") (pin "54") (pinfunction "54_54") (pintype "input+no_connect"))
    )
    (net (code "248") (name "unconnected-(J37-Pad55)") (class "Default")
      (node (ref "J37") (pin "55") (pinfunction "55_55") (pintype "input+no_connect"))
    )
    (net (code "249") (name "unconnected-(J37-Pad56)") (class "Default")
      (node (ref "J37") (pin "56") (pinfunction "56_56") (pintype "input+no_connect"))
    )
    (net (code "250") (name "unconnected-(J37-Pad57)") (class "Default")
      (node (ref "J37") (pin "57") (pinfunction "57_57") (pintype "input+no_connect"))
    )
    (net (code "251") (name "unconnected-(J37-Pad58)") (class "Default")
      (node (ref "J37") (pin "58") (pinfunction "58_58") (pintype "input+no_connect"))
    )
    (net (code "252") (name "unconnected-(J37-Pad61)") (class "Default")
      (node (ref "J37") (pin "61") (pinfunction "61_61") (pintype "input+no_connect"))
    )
    (net (code "253") (name "unconnected-(J37-Pad62)") (class "Default")
      (node (ref "J37") (pin "62") (pinfunction "62_62") (pintype "input+no_connect"))
    )
    (net (code "254") (name "unconnected-(J37-Pad63)") (class "Default")
      (node (ref "J37") (pin "63") (pinfunction "63_63") (pintype "input+no_connect"))
    )
    (net (code "255") (name "unconnected-(J37-Pad64)") (class "Default")
      (node (ref "J37") (pin "64") (pinfunction "64_64") (pintype "input+no_connect"))
    )
    (net (code "256") (name "unconnected-(J37-Pad65)") (class "Default")
      (node (ref "J37") (pin "65") (pinfunction "65_65") (pintype "input+no_connect"))
    )
    (net (code "257") (name "unconnected-(J37-Pad66)") (class "Default")
      (node (ref "J37") (pin "66") (pinfunction "66_66") (pintype "input+no_connect"))
    )
    (net (code "258") (name "unconnected-(J37-Pad67)") (class "Default")
      (node (ref "J37") (pin "67") (pinfunction "67_67") (pintype "input+no_connect"))
    )
    (net (code "259") (name "unconnected-(J37-Pad68)") (class "Default")
      (node (ref "J37") (pin "68") (pinfunction "68_68") (pintype "input+no_connect"))
    )
    (net (code "260") (name "unconnected-(J37-Pad71)") (class "Default")
      (node (ref "J37") (pin "71") (pinfunction "71_71") (pintype "input+no_connect"))
    )
    (net (code "261") (name "unconnected-(J37-Pad72)") (class "Default")
      (node (ref "J37") (pin "72") (pinfunction "72_72") (pintype "input+no_connect"))
    )
    (net (code "262") (name "unconnected-(J37-Pad73)") (class "Default")
      (node (ref "J37") (pin "73") (pinfunction "73_73") (pintype "input+no_connect"))
    )
    (net (code "263") (name "unconnected-(J37-Pad74)") (class "Default")
      (node (ref "J37") (pin "74") (pinfunction "74_74") (pintype "input+no_connect"))
    )
    (net (code "264") (name "unconnected-(J37-Pad75)") (class "Default")
      (node (ref "J37") (pin "75") (pinfunction "75_75") (pintype "input+no_connect"))
    )
    (net (code "265") (name "unconnected-(J37-Pad76)") (class "Default")
      (node (ref "J37") (pin "76") (pinfunction "76_76") (pintype "input+no_connect"))
    )
    (net (code "266") (name "unconnected-(J37-Pad77)") (class "Default")
      (node (ref "J37") (pin "77") (pinfunction "77_77") (pintype "input+no_connect"))
    )
    (net (code "267") (name "unconnected-(J37-Pad78)") (class "Default")
      (node (ref "J37") (pin "78") (pinfunction "78_78") (pintype "input+no_connect"))
    )
    (net (code "268") (name "unconnected-(J37-Pad79)") (class "Default")
      (node (ref "J37") (pin "79") (pinfunction "79_79") (pintype "input+no_connect"))
    )
    (net (code "269") (name "unconnected-(J37-Pad80)") (class "Default")
      (node (ref "J37") (pin "80") (pinfunction "80_80") (pintype "input+no_connect"))
    )
    (net (code "270") (name "unconnected-(J37-Pad81)") (class "Default")
      (node (ref "J37") (pin "81") (pinfunction "81_81") (pintype "input+no_connect"))
    )
    (net (code "271") (name "unconnected-(J37-Pad82)") (class "Default")
      (node (ref "J37") (pin "82") (pinfunction "82_82") (pintype "input+no_connect"))
    )
    (net (code "272") (name "unconnected-(J37-Pad83)") (class "Default")
      (node (ref "J37") (pin "83") (pinfunction "83_83") (pintype "input+no_connect"))
    )
    (net (code "273") (name "unconnected-(J37-Pad84)") (class "Default")
      (node (ref "J37") (pin "84") (pinfunction "84_84") (pintype "input+no_connect"))
    )
  )
)
